# Main.net
KiCad netlist of a schematic drawn in Altium Designer
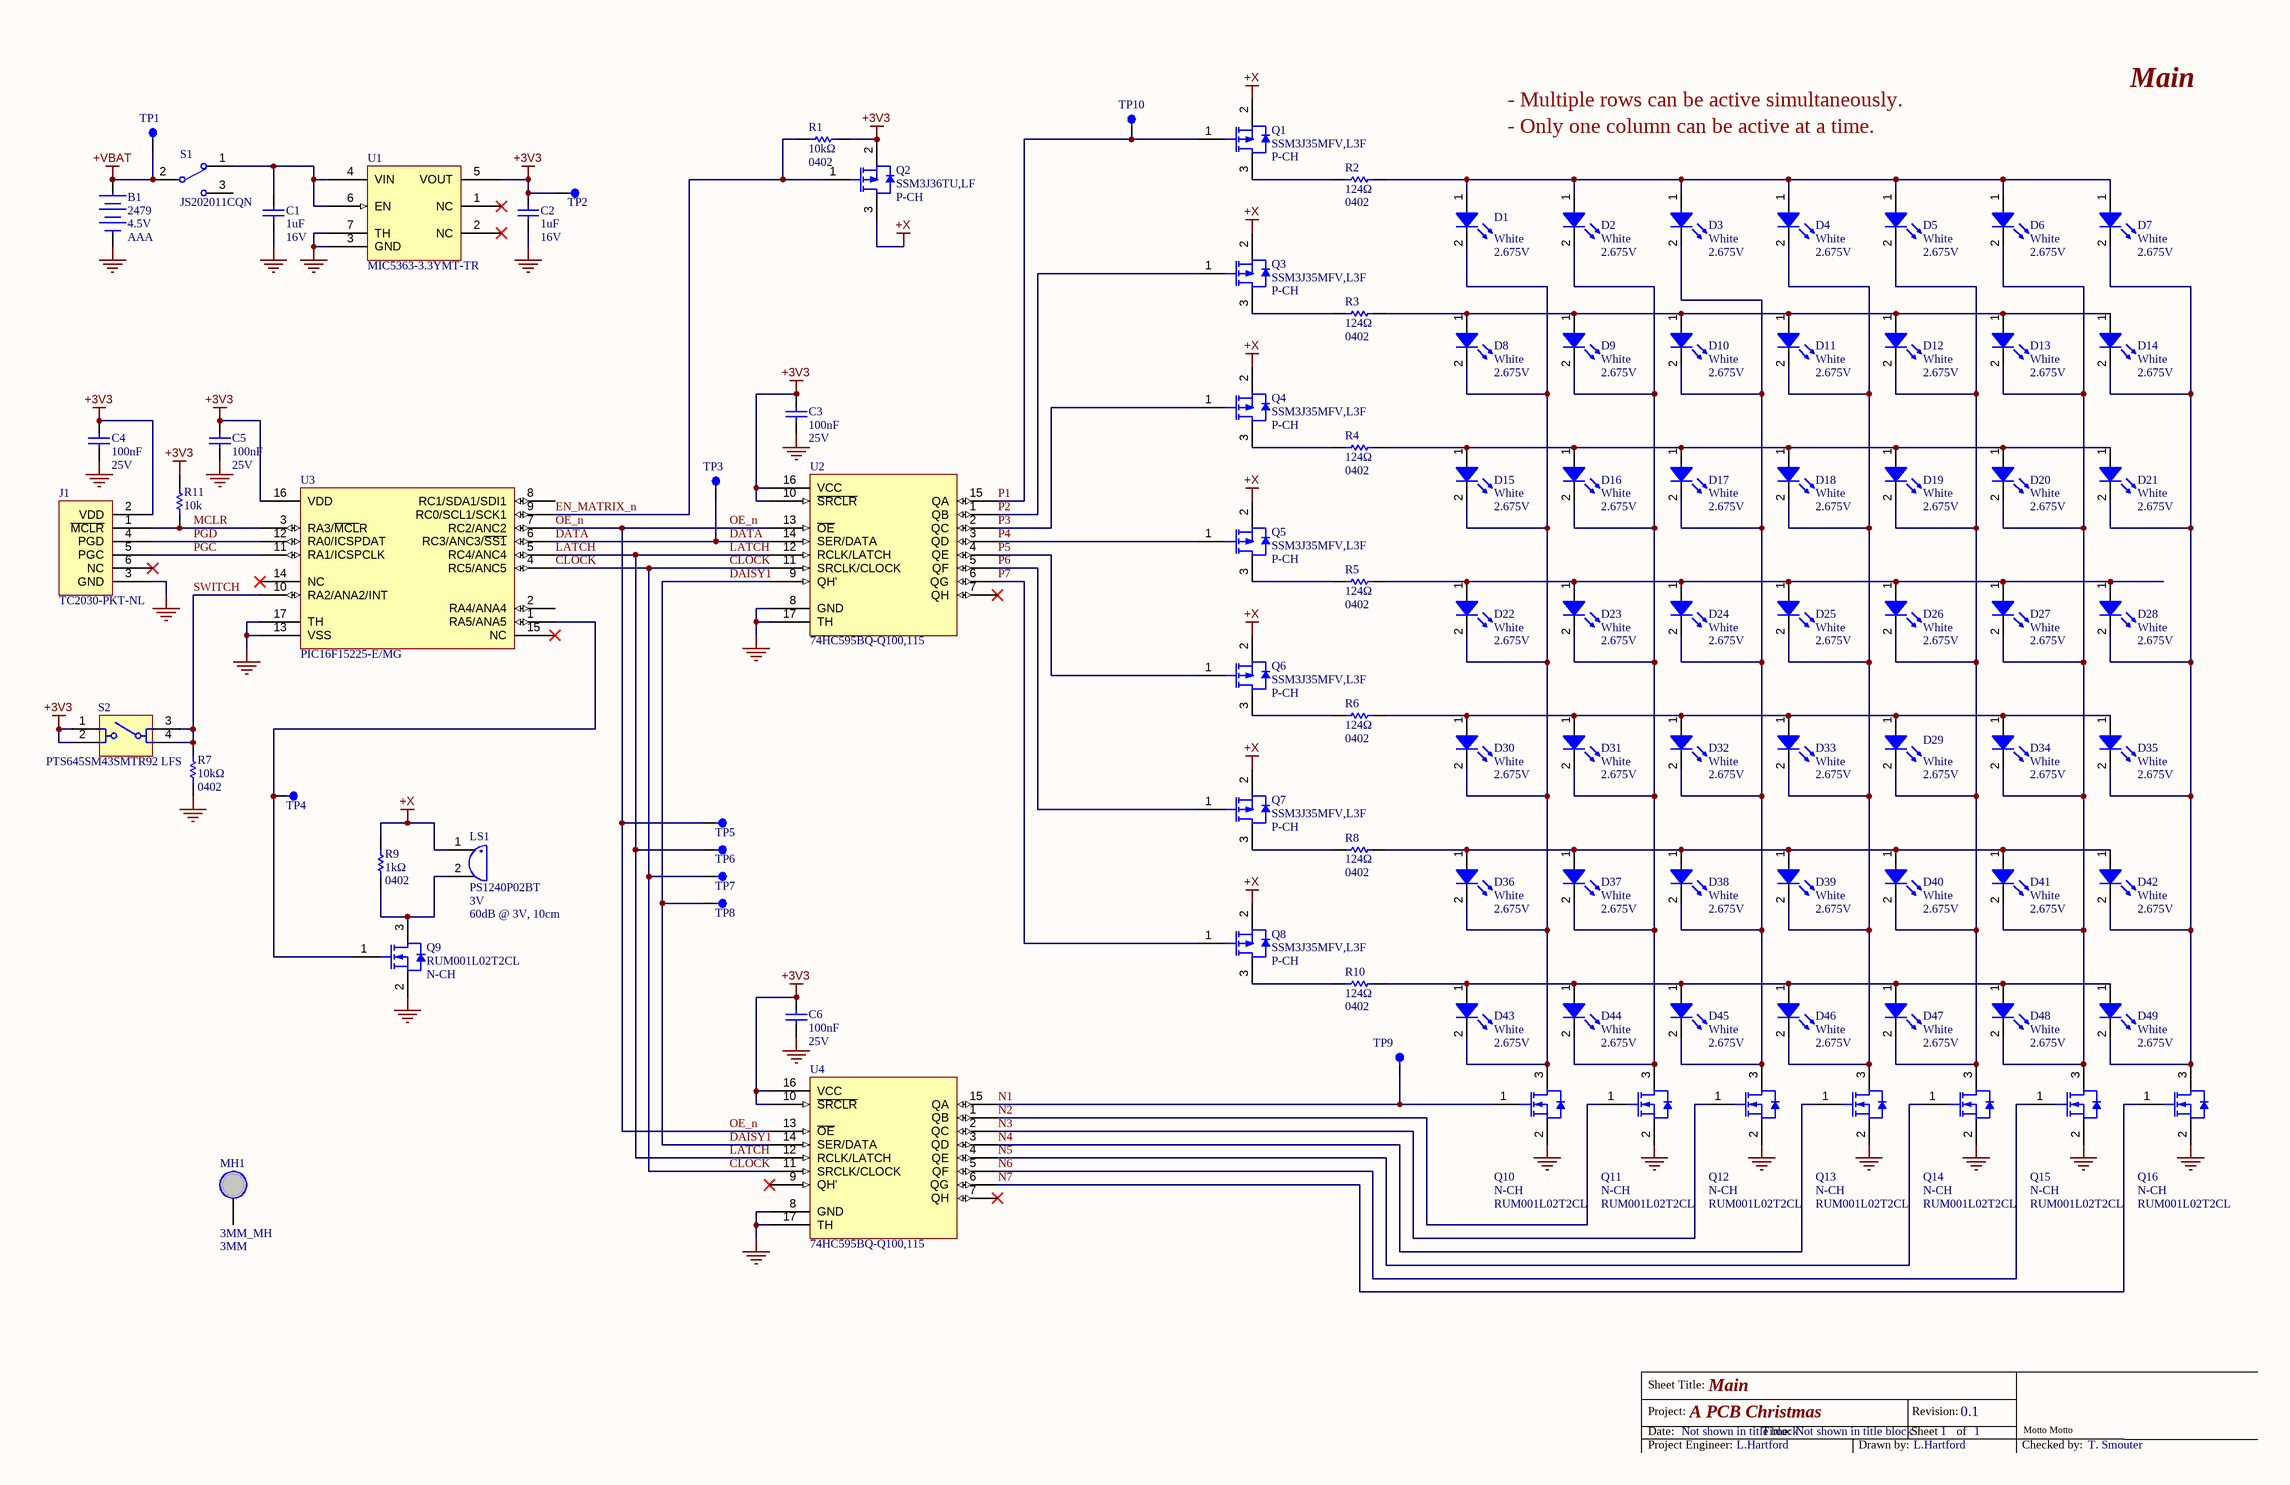
[diagram p0: Main.SchDoc]

(export (version "E")
  (design (tool "Eeschema 10.0.6"))
  (components
    (comp (ref "B1")
      (value "Three Cell")
      (footprint "2479")
      (fields
        (field (name "=MANUFACTURER PART NUMBER") "2479")
        (field (name "V") "4.5V")
        (field (name "SERIES") "AAA")
        (field (name "PART NUMBER") "2479")
        (field (name "VOLTAGE") "4.5V")
      )
      (libsource (lib "altium-db-library") (part "Three Cell"))
    )
    (comp (ref "C1")
      (value "1uF")
      (footprint "C0402")
      (fields
        (field (name "VOLTAGE") "16V")
        (field (name "PART NUMBER") "CL05A105KO5NNNC")
        (field (name "MANUFACTURER") "Samsung Electro-Mechanics")
        (field (name "Comment") "Ceramic Cap")
      )
      (libsource (lib "altium-db-library") (part "Ceramic Cap"))
    )
    (comp (ref "C2")
      (value "1uF")
      (footprint "C0402")
      (fields
        (field (name "VOLTAGE") "16V")
        (field (name "PART NUMBER") "CL05A105KO5NNNC")
        (field (name "MANUFACTURER") "Samsung Electro-Mechanics")
        (field (name "Comment") "Ceramic Cap")
      )
      (libsource (lib "altium-db-library") (part "Ceramic Cap"))
    )
    (comp (ref "C3")
      (value "100nF")
      (footprint "C0402")
      (fields
        (field (name "VOLTAGE") "25V")
        (field (name "PART NUMBER") "CL05A104KA5NNNC")
        (field (name "MANUFACTURER") "Samsung Electro-Mechanics")
        (field (name "Comment") "Ceramic Cap")
      )
      (libsource (lib "altium-db-library") (part "Ceramic Cap"))
    )
    (comp (ref "C4")
      (value "100nF")
      (footprint "C0402")
      (fields
        (field (name "VOLTAGE") "25V")
        (field (name "PART NUMBER") "CL05A104KA5NNNC")
        (field (name "MANUFACTURER") "Samsung Electro-Mechanics")
        (field (name "Comment") "Ceramic Cap")
      )
      (libsource (lib "altium-db-library") (part "Ceramic Cap"))
    )
    (comp (ref "C5")
      (value "100nF")
      (footprint "C0402")
      (fields
        (field (name "VOLTAGE") "25V")
        (field (name "PART NUMBER") "CL05A104KA5NNNC")
        (field (name "MANUFACTURER") "Samsung Electro-Mechanics")
        (field (name "Comment") "Ceramic Cap")
      )
      (libsource (lib "altium-db-library") (part "Ceramic Cap"))
    )
    (comp (ref "C6")
      (value "100nF")
      (footprint "C0402")
      (fields
        (field (name "VOLTAGE") "25V")
        (field (name "PART NUMBER") "CL05A104KA5NNNC")
        (field (name "MANUFACTURER") "Samsung Electro-Mechanics")
        (field (name "Comment") "Ceramic Cap")
      )
      (libsource (lib "altium-db-library") (part "Ceramic Cap"))
    )
    (comp (ref "D1")
      (value "LED")
      (footprint "16-219AUTD/S3151/TR8")
      (fields
        (field (name "MANUFACTURER PART NUMBER") "16-219AUTD/S3151/TR8")
        (field (name "COLOR") "White")
        (field (name "FORWARD") "2.675V")
      )
      (libsource (lib "altium-db-library") (part "LED"))
    )
    (comp (ref "D2")
      (value "LED")
      (footprint "16-219AUTD/S3151/TR8")
      (fields
        (field (name "MANUFACTURER PART NUMBER") "16-219AUTD/S3151/TR8")
        (field (name "COLOR") "White")
        (field (name "FORWARD") "2.675V")
      )
      (libsource (lib "altium-db-library") (part "LED"))
    )
    (comp (ref "D3")
      (value "LED")
      (footprint "16-219AUTD/S3151/TR8")
      (fields
        (field (name "MANUFACTURER PART NUMBER") "16-219AUTD/S3151/TR8")
        (field (name "COLOR") "White")
        (field (name "FORWARD") "2.675V")
      )
      (libsource (lib "altium-db-library") (part "LED"))
    )
    (comp (ref "D4")
      (value "LED")
      (footprint "16-219AUTD/S3151/TR8")
      (fields
        (field (name "MANUFACTURER PART NUMBER") "16-219AUTD/S3151/TR8")
        (field (name "COLOR") "White")
        (field (name "FORWARD") "2.675V")
      )
      (libsource (lib "altium-db-library") (part "LED"))
    )
    (comp (ref "D5")
      (value "LED")
      (footprint "16-219AUTD/S3151/TR8")
      (fields
        (field (name "MANUFACTURER PART NUMBER") "16-219AUTD/S3151/TR8")
        (field (name "COLOR") "White")
        (field (name "FORWARD") "2.675V")
      )
      (libsource (lib "altium-db-library") (part "LED"))
    )
    (comp (ref "D6")
      (value "LED")
      (footprint "16-219AUTD/S3151/TR8")
      (fields
        (field (name "MANUFACTURER PART NUMBER") "16-219AUTD/S3151/TR8")
        (field (name "COLOR") "White")
        (field (name "FORWARD") "2.675V")
      )
      (libsource (lib "altium-db-library") (part "LED"))
    )
    (comp (ref "D7")
      (value "LED")
      (footprint "16-219AUTD/S3151/TR8")
      (fields
        (field (name "MANUFACTURER PART NUMBER") "16-219AUTD/S3151/TR8")
        (field (name "COLOR") "White")
        (field (name "FORWARD") "2.675V")
      )
      (libsource (lib "altium-db-library") (part "LED"))
    )
    (comp (ref "D8")
      (value "LED")
      (footprint "16-219AUTD/S3151/TR8")
      (fields
        (field (name "MANUFACTURER PART NUMBER") "16-219AUTD/S3151/TR8")
        (field (name "COLOR") "White")
        (field (name "FORWARD") "2.675V")
      )
      (libsource (lib "altium-db-library") (part "LED"))
    )
    (comp (ref "D9")
      (value "LED")
      (footprint "16-219AUTD/S3151/TR8")
      (fields
        (field (name "MANUFACTURER PART NUMBER") "16-219AUTD/S3151/TR8")
        (field (name "COLOR") "White")
        (field (name "FORWARD") "2.675V")
      )
      (libsource (lib "altium-db-library") (part "LED"))
    )
    (comp (ref "D10")
      (value "LED")
      (footprint "16-219AUTD/S3151/TR8")
      (fields
        (field (name "MANUFACTURER PART NUMBER") "16-219AUTD/S3151/TR8")
        (field (name "COLOR") "White")
        (field (name "FORWARD") "2.675V")
      )
      (libsource (lib "altium-db-library") (part "LED"))
    )
    (comp (ref "D11")
      (value "LED")
      (footprint "16-219AUTD/S3151/TR8")
      (fields
        (field (name "MANUFACTURER PART NUMBER") "16-219AUTD/S3151/TR8")
        (field (name "COLOR") "White")
        (field (name "FORWARD") "2.675V")
      )
      (libsource (lib "altium-db-library") (part "LED"))
    )
    (comp (ref "D12")
      (value "LED")
      (footprint "16-219AUTD/S3151/TR8")
      (fields
        (field (name "MANUFACTURER PART NUMBER") "16-219AUTD/S3151/TR8")
        (field (name "COLOR") "White")
        (field (name "FORWARD") "2.675V")
      )
      (libsource (lib "altium-db-library") (part "LED"))
    )
    (comp (ref "D13")
      (value "LED")
      (footprint "16-219AUTD/S3151/TR8")
      (fields
        (field (name "MANUFACTURER PART NUMBER") "16-219AUTD/S3151/TR8")
        (field (name "COLOR") "White")
        (field (name "FORWARD") "2.675V")
      )
      (libsource (lib "altium-db-library") (part "LED"))
    )
    (comp (ref "D14")
      (value "LED")
      (footprint "16-219AUTD/S3151/TR8")
      (fields
        (field (name "MANUFACTURER PART NUMBER") "16-219AUTD/S3151/TR8")
        (field (name "COLOR") "White")
        (field (name "FORWARD") "2.675V")
      )
      (libsource (lib "altium-db-library") (part "LED"))
    )
    (comp (ref "D15")
      (value "LED")
      (footprint "16-219AUTD/S3151/TR8")
      (fields
        (field (name "MANUFACTURER PART NUMBER") "16-219AUTD/S3151/TR8")
        (field (name "COLOR") "White")
        (field (name "FORWARD") "2.675V")
      )
      (libsource (lib "altium-db-library") (part "LED"))
    )
    (comp (ref "D16")
      (value "LED")
      (footprint "16-219AUTD/S3151/TR8")
      (fields
        (field (name "MANUFACTURER PART NUMBER") "16-219AUTD/S3151/TR8")
        (field (name "COLOR") "White")
        (field (name "FORWARD") "2.675V")
      )
      (libsource (lib "altium-db-library") (part "LED"))
    )
    (comp (ref "D17")
      (value "LED")
      (footprint "16-219AUTD/S3151/TR8")
      (fields
        (field (name "MANUFACTURER PART NUMBER") "16-219AUTD/S3151/TR8")
        (field (name "COLOR") "White")
        (field (name "FORWARD") "2.675V")
      )
      (libsource (lib "altium-db-library") (part "LED"))
    )
    (comp (ref "D18")
      (value "LED")
      (footprint "16-219AUTD/S3151/TR8")
      (fields
        (field (name "MANUFACTURER PART NUMBER") "16-219AUTD/S3151/TR8")
        (field (name "COLOR") "White")
        (field (name "FORWARD") "2.675V")
      )
      (libsource (lib "altium-db-library") (part "LED"))
    )
    (comp (ref "D19")
      (value "LED")
      (footprint "16-219AUTD/S3151/TR8")
      (fields
        (field (name "MANUFACTURER PART NUMBER") "16-219AUTD/S3151/TR8")
        (field (name "COLOR") "White")
        (field (name "FORWARD") "2.675V")
      )
      (libsource (lib "altium-db-library") (part "LED"))
    )
    (comp (ref "D20")
      (value "LED")
      (footprint "16-219AUTD/S3151/TR8")
      (fields
        (field (name "MANUFACTURER PART NUMBER") "16-219AUTD/S3151/TR8")
        (field (name "COLOR") "White")
        (field (name "FORWARD") "2.675V")
      )
      (libsource (lib "altium-db-library") (part "LED"))
    )
    (comp (ref "D21")
      (value "LED")
      (footprint "16-219AUTD/S3151/TR8")
      (fields
        (field (name "MANUFACTURER PART NUMBER") "16-219AUTD/S3151/TR8")
        (field (name "COLOR") "White")
        (field (name "FORWARD") "2.675V")
      )
      (libsource (lib "altium-db-library") (part "LED"))
    )
    (comp (ref "D22")
      (value "LED")
      (footprint "16-219AUTD/S3151/TR8")
      (fields
        (field (name "MANUFACTURER PART NUMBER") "16-219AUTD/S3151/TR8")
        (field (name "COLOR") "White")
        (field (name "FORWARD") "2.675V")
      )
      (libsource (lib "altium-db-library") (part "LED"))
    )
    (comp (ref "D23")
      (value "LED")
      (footprint "16-219AUTD/S3151/TR8")
      (fields
        (field (name "MANUFACTURER PART NUMBER") "16-219AUTD/S3151/TR8")
        (field (name "COLOR") "White")
        (field (name "FORWARD") "2.675V")
      )
      (libsource (lib "altium-db-library") (part "LED"))
    )
    (comp (ref "D24")
      (value "LED")
      (footprint "16-219AUTD/S3151/TR8")
      (fields
        (field (name "MANUFACTURER PART NUMBER") "16-219AUTD/S3151/TR8")
        (field (name "COLOR") "White")
        (field (name "FORWARD") "2.675V")
      )
      (libsource (lib "altium-db-library") (part "LED"))
    )
    (comp (ref "D25")
      (value "LED")
      (footprint "16-219AUTD/S3151/TR8")
      (fields
        (field (name "MANUFACTURER PART NUMBER") "16-219AUTD/S3151/TR8")
        (field (name "COLOR") "White")
        (field (name "FORWARD") "2.675V")
      )
      (libsource (lib "altium-db-library") (part "LED"))
    )
    (comp (ref "D26")
      (value "LED")
      (footprint "16-219AUTD/S3151/TR8")
      (fields
        (field (name "MANUFACTURER PART NUMBER") "16-219AUTD/S3151/TR8")
        (field (name "COLOR") "White")
        (field (name "FORWARD") "2.675V")
      )
      (libsource (lib "altium-db-library") (part "LED"))
    )
    (comp (ref "D27")
      (value "LED")
      (footprint "16-219AUTD/S3151/TR8")
      (fields
        (field (name "MANUFACTURER PART NUMBER") "16-219AUTD/S3151/TR8")
        (field (name "COLOR") "White")
        (field (name "FORWARD") "2.675V")
      )
      (libsource (lib "altium-db-library") (part "LED"))
    )
    (comp (ref "D28")
      (value "LED")
      (footprint "16-219AUTD/S3151/TR8")
      (fields
        (field (name "MANUFACTURER PART NUMBER") "16-219AUTD/S3151/TR8")
        (field (name "COLOR") "White")
        (field (name "FORWARD") "2.675V")
      )
      (libsource (lib "altium-db-library") (part "LED"))
    )
    (comp (ref "D29")
      (value "LED")
      (footprint "16-219AUTD/S3151/TR8")
      (fields
        (field (name "MANUFACTURER PART NUMBER") "16-219AUTD/S3151/TR8")
        (field (name "COLOR") "White")
        (field (name "FORWARD") "2.675V")
      )
      (libsource (lib "altium-db-library") (part "LED"))
    )
    (comp (ref "D30")
      (value "LED")
      (footprint "16-219AUTD/S3151/TR8")
      (fields
        (field (name "MANUFACTURER PART NUMBER") "16-219AUTD/S3151/TR8")
        (field (name "COLOR") "White")
        (field (name "FORWARD") "2.675V")
      )
      (libsource (lib "altium-db-library") (part "LED"))
    )
    (comp (ref "D31")
      (value "LED")
      (footprint "16-219AUTD/S3151/TR8")
      (fields
        (field (name "MANUFACTURER PART NUMBER") "16-219AUTD/S3151/TR8")
        (field (name "COLOR") "White")
        (field (name "FORWARD") "2.675V")
      )
      (libsource (lib "altium-db-library") (part "LED"))
    )
    (comp (ref "D32")
      (value "LED")
      (footprint "16-219AUTD/S3151/TR8")
      (fields
        (field (name "MANUFACTURER PART NUMBER") "16-219AUTD/S3151/TR8")
        (field (name "COLOR") "White")
        (field (name "FORWARD") "2.675V")
      )
      (libsource (lib "altium-db-library") (part "LED"))
    )
    (comp (ref "D33")
      (value "LED")
      (footprint "16-219AUTD/S3151/TR8")
      (fields
        (field (name "MANUFACTURER PART NUMBER") "16-219AUTD/S3151/TR8")
        (field (name "COLOR") "White")
        (field (name "FORWARD") "2.675V")
      )
      (libsource (lib "altium-db-library") (part "LED"))
    )
    (comp (ref "D34")
      (value "LED")
      (footprint "16-219AUTD/S3151/TR8")
      (fields
        (field (name "MANUFACTURER PART NUMBER") "16-219AUTD/S3151/TR8")
        (field (name "COLOR") "White")
        (field (name "FORWARD") "2.675V")
      )
      (libsource (lib "altium-db-library") (part "LED"))
    )
    (comp (ref "D35")
      (value "LED")
      (footprint "16-219AUTD/S3151/TR8")
      (fields
        (field (name "MANUFACTURER PART NUMBER") "16-219AUTD/S3151/TR8")
        (field (name "COLOR") "White")
        (field (name "FORWARD") "2.675V")
      )
      (libsource (lib "altium-db-library") (part "LED"))
    )
    (comp (ref "D36")
      (value "LED")
      (footprint "16-219AUTD/S3151/TR8")
      (fields
        (field (name "MANUFACTURER PART NUMBER") "16-219AUTD/S3151/TR8")
        (field (name "COLOR") "White")
        (field (name "FORWARD") "2.675V")
      )
      (libsource (lib "altium-db-library") (part "LED"))
    )
    (comp (ref "D37")
      (value "LED")
      (footprint "16-219AUTD/S3151/TR8")
      (fields
        (field (name "MANUFACTURER PART NUMBER") "16-219AUTD/S3151/TR8")
        (field (name "COLOR") "White")
        (field (name "FORWARD") "2.675V")
      )
      (libsource (lib "altium-db-library") (part "LED"))
    )
    (comp (ref "D38")
      (value "LED")
      (footprint "16-219AUTD/S3151/TR8")
      (fields
        (field (name "MANUFACTURER PART NUMBER") "16-219AUTD/S3151/TR8")
        (field (name "COLOR") "White")
        (field (name "FORWARD") "2.675V")
      )
      (libsource (lib "altium-db-library") (part "LED"))
    )
    (comp (ref "D39")
      (value "LED")
      (footprint "16-219AUTD/S3151/TR8")
      (fields
        (field (name "MANUFACTURER PART NUMBER") "16-219AUTD/S3151/TR8")
        (field (name "COLOR") "White")
        (field (name "FORWARD") "2.675V")
      )
      (libsource (lib "altium-db-library") (part "LED"))
    )
    (comp (ref "D40")
      (value "LED")
      (footprint "16-219AUTD/S3151/TR8")
      (fields
        (field (name "MANUFACTURER PART NUMBER") "16-219AUTD/S3151/TR8")
        (field (name "COLOR") "White")
        (field (name "FORWARD") "2.675V")
      )
      (libsource (lib "altium-db-library") (part "LED"))
    )
    (comp (ref "D41")
      (value "LED")
      (footprint "16-219AUTD/S3151/TR8")
      (fields
        (field (name "MANUFACTURER PART NUMBER") "16-219AUTD/S3151/TR8")
        (field (name "COLOR") "White")
        (field (name "FORWARD") "2.675V")
      )
      (libsource (lib "altium-db-library") (part "LED"))
    )
    (comp (ref "D42")
      (value "LED")
      (footprint "16-219AUTD/S3151/TR8")
      (fields
        (field (name "MANUFACTURER PART NUMBER") "16-219AUTD/S3151/TR8")
        (field (name "COLOR") "White")
        (field (name "FORWARD") "2.675V")
      )
      (libsource (lib "altium-db-library") (part "LED"))
    )
    (comp (ref "D43")
      (value "LED")
      (footprint "16-219AUTD/S3151/TR8")
      (fields
        (field (name "MANUFACTURER PART NUMBER") "16-219AUTD/S3151/TR8")
        (field (name "COLOR") "White")
        (field (name "FORWARD") "2.675V")
      )
      (libsource (lib "altium-db-library") (part "LED"))
    )
    (comp (ref "D44")
      (value "LED")
      (footprint "16-219AUTD/S3151/TR8")
      (fields
        (field (name "MANUFACTURER PART NUMBER") "16-219AUTD/S3151/TR8")
        (field (name "COLOR") "White")
        (field (name "FORWARD") "2.675V")
      )
      (libsource (lib "altium-db-library") (part "LED"))
    )
    (comp (ref "D45")
      (value "LED")
      (footprint "16-219AUTD/S3151/TR8")
      (fields
        (field (name "MANUFACTURER PART NUMBER") "16-219AUTD/S3151/TR8")
        (field (name "COLOR") "White")
        (field (name "FORWARD") "2.675V")
      )
      (libsource (lib "altium-db-library") (part "LED"))
    )
    (comp (ref "D46")
      (value "LED")
      (footprint "16-219AUTD/S3151/TR8")
      (fields
        (field (name "MANUFACTURER PART NUMBER") "16-219AUTD/S3151/TR8")
        (field (name "COLOR") "White")
        (field (name "FORWARD") "2.675V")
      )
      (libsource (lib "altium-db-library") (part "LED"))
    )
    (comp (ref "D47")
      (value "LED")
      (footprint "16-219AUTD/S3151/TR8")
      (fields
        (field (name "MANUFACTURER PART NUMBER") "16-219AUTD/S3151/TR8")
        (field (name "COLOR") "White")
        (field (name "FORWARD") "2.675V")
      )
      (libsource (lib "altium-db-library") (part "LED"))
    )
    (comp (ref "D48")
      (value "LED")
      (footprint "16-219AUTD/S3151/TR8")
      (fields
        (field (name "MANUFACTURER PART NUMBER") "16-219AUTD/S3151/TR8")
        (field (name "COLOR") "White")
        (field (name "FORWARD") "2.675V")
      )
      (libsource (lib "altium-db-library") (part "LED"))
    )
    (comp (ref "D49")
      (value "LED")
      (footprint "16-219AUTD/S3151/TR8")
      (fields
        (field (name "MANUFACTURER PART NUMBER") "16-219AUTD/S3151/TR8")
        (field (name "COLOR") "White")
        (field (name "FORWARD") "2.675V")
      )
      (libsource (lib "altium-db-library") (part "LED"))
    )
    (comp (ref "J1")
      (value "TC2030-PKT-NL")
      (footprint "TC2030-PKT-NL")
      (description "No Clip 6 Pin Tag Connect")
      (fields (field (name "MANUFACTURER") "Tag-Connect LLC"))
      (libsource (lib "altium-db-library") (part "TC2030-PKT-NL"))
    )
    (comp (ref "LS1")
      (value "Buzzer")
      (footprint "PS1240P02BT")
      (fields
        (field (name "MANUFACTURER PART NUMBER") "PS1240P02BT")
        (field (name "VOLTAGE") "3V")
        (field (name "SOUND PRESSURE LEVEL") "60dB @ 3V, 10cm")
        (field (name "PART NUMBER") "PS1240P02BT")
      )
      (libsource (lib "altium-db-library") (part "Buzzer"))
    )
    (comp (ref "MH1")
      (value "3MM_MH")
      (footprint "3MM_MH")
      (fields (field (name "SIZE") "3MM"))
      (libsource (lib "altium-db-library") (part "3MM_MH"))
    )
    (comp (ref "Q1")
      (value "P-CH")
      (footprint "SOTFL40P120X55-3N-2")
      (fields
        (field (name "MANUFACTURER PART NUMBER") "SSM3J35MFV,L3F")
        (field (name "FET TYPE") "P-CH")
        (field (name "PART NUMBER") "SSM3J35MFV,L3F")
        (field (name "MANUFACTURER") "Toshiba Semiconductor and Storage")
      )
      (libsource (lib "altium-db-library") (part "P-CH"))
    )
    (comp (ref "Q2")
      (value "P-CH")
      (footprint "SOTFL65P210X75-3N")
      (fields
        (field (name "MANUFACTURER PART NUMBER") "SSM3J36TU,LF")
        (field (name "FET TYPE") "P-CH")
        (field (name "PART NUMBER") "SSM3J36TU,LF")
        (field (name "MANUFACTURER") "Toshiba Semiconductor and Storage")
      )
      (libsource (lib "altium-db-library") (part "P-CH"))
    )
    (comp (ref "Q3")
      (value "P-CH")
      (footprint "SOTFL40P120X55-3N-2")
      (fields
        (field (name "MANUFACTURER PART NUMBER") "SSM3J35MFV,L3F")
        (field (name "FET TYPE") "P-CH")
        (field (name "PART NUMBER") "SSM3J35MFV,L3F")
        (field (name "MANUFACTURER") "Toshiba Semiconductor and Storage")
      )
      (libsource (lib "altium-db-library") (part "P-CH"))
    )
    (comp (ref "Q4")
      (value "P-CH")
      (footprint "SOTFL40P120X55-3N-2")
      (fields
        (field (name "MANUFACTURER PART NUMBER") "SSM3J35MFV,L3F")
        (field (name "FET TYPE") "P-CH")
        (field (name "PART NUMBER") "SSM3J35MFV,L3F")
        (field (name "MANUFACTURER") "Toshiba Semiconductor and Storage")
      )
      (libsource (lib "altium-db-library") (part "P-CH"))
    )
    (comp (ref "Q5")
      (value "P-CH")
      (footprint "SOTFL40P120X55-3N-2")
      (fields
        (field (name "MANUFACTURER PART NUMBER") "SSM3J35MFV,L3F")
        (field (name "FET TYPE") "P-CH")
        (field (name "PART NUMBER") "SSM3J35MFV,L3F")
        (field (name "MANUFACTURER") "Toshiba Semiconductor and Storage")
      )
      (libsource (lib "altium-db-library") (part "P-CH"))
    )
    (comp (ref "Q6")
      (value "P-CH")
      (footprint "SOTFL40P120X55-3N-2")
      (fields
        (field (name "MANUFACTURER PART NUMBER") "SSM3J35MFV,L3F")
        (field (name "FET TYPE") "P-CH")
        (field (name "PART NUMBER") "SSM3J35MFV,L3F")
        (field (name "MANUFACTURER") "Toshiba Semiconductor and Storage")
      )
      (libsource (lib "altium-db-library") (part "P-CH"))
    )
    (comp (ref "Q7")
      (value "P-CH")
      (footprint "SOTFL40P120X55-3N-2")
      (fields
        (field (name "MANUFACTURER PART NUMBER") "SSM3J35MFV,L3F")
        (field (name "FET TYPE") "P-CH")
        (field (name "PART NUMBER") "SSM3J35MFV,L3F")
        (field (name "MANUFACTURER") "Toshiba Semiconductor and Storage")
      )
      (libsource (lib "altium-db-library") (part "P-CH"))
    )
    (comp (ref "Q8")
      (value "P-CH")
      (footprint "SOTFL40P120X55-3N-2")
      (fields
        (field (name "MANUFACTURER PART NUMBER") "SSM3J35MFV,L3F")
        (field (name "FET TYPE") "P-CH")
        (field (name "PART NUMBER") "SSM3J35MFV,L3F")
        (field (name "MANUFACTURER") "Toshiba Semiconductor and Storage")
      )
      (libsource (lib "altium-db-library") (part "P-CH"))
    )
    (comp (ref "Q9")
      (value "N-CH")
      (footprint "SOTFL40P120X55-3N")
      (fields
        (field (name "MANUFACTURER PART NUMBER") "RUM001L02T2CL")
        (field (name "FET TYPE") "N-CH")
        (field (name "PART NUMBER") "RUM001L02T2CL")
        (field (name "MANUFACTURER") "Rohm Semiconductor")
      )
      (libsource (lib "altium-db-library") (part "N-CH"))
    )
    (comp (ref "Q10")
      (value "N-CH")
      (footprint "SOTFL40P120X55-3N")
      (fields
        (field (name "MANUFACTURER PART NUMBER") "RUM001L02T2CL")
        (field (name "FET TYPE") "N-CH")
        (field (name "PART NUMBER") "RUM001L02T2CL")
        (field (name "MANUFACTURER") "Rohm Semiconductor")
      )
      (libsource (lib "altium-db-library") (part "N-CH"))
    )
    (comp (ref "Q11")
      (value "N-CH")
      (footprint "SOTFL40P120X55-3N")
      (fields
        (field (name "MANUFACTURER PART NUMBER") "RUM001L02T2CL")
        (field (name "FET TYPE") "N-CH")
        (field (name "PART NUMBER") "RUM001L02T2CL")
        (field (name "MANUFACTURER") "Rohm Semiconductor")
      )
      (libsource (lib "altium-db-library") (part "N-CH"))
    )
    (comp (ref "Q12")
      (value "N-CH")
      (footprint "SOTFL40P120X55-3N")
      (fields
        (field (name "MANUFACTURER PART NUMBER") "RUM001L02T2CL")
        (field (name "FET TYPE") "N-CH")
        (field (name "PART NUMBER") "RUM001L02T2CL")
        (field (name "MANUFACTURER") "Rohm Semiconductor")
      )
      (libsource (lib "altium-db-library") (part "N-CH"))
    )
    (comp (ref "Q13")
      (value "N-CH")
      (footprint "SOTFL40P120X55-3N")
      (fields
        (field (name "MANUFACTURER PART NUMBER") "RUM001L02T2CL")
        (field (name "FET TYPE") "N-CH")
        (field (name "PART NUMBER") "RUM001L02T2CL")
        (field (name "MANUFACTURER") "Rohm Semiconductor")
      )
      (libsource (lib "altium-db-library") (part "N-CH"))
    )
    (comp (ref "Q14")
      (value "N-CH")
      (footprint "SOTFL40P120X55-3N")
      (fields
        (field (name "MANUFACTURER PART NUMBER") "RUM001L02T2CL")
        (field (name "FET TYPE") "N-CH")
        (field (name "PART NUMBER") "RUM001L02T2CL")
        (field (name "MANUFACTURER") "Rohm Semiconductor")
      )
      (libsource (lib "altium-db-library") (part "N-CH"))
    )
    (comp (ref "Q15")
      (value "N-CH")
      (footprint "SOTFL40P120X55-3N")
      (fields
        (field (name "MANUFACTURER PART NUMBER") "RUM001L02T2CL")
        (field (name "FET TYPE") "N-CH")
        (field (name "PART NUMBER") "RUM001L02T2CL")
        (field (name "MANUFACTURER") "Rohm Semiconductor")
      )
      (libsource (lib "altium-db-library") (part "N-CH"))
    )
    (comp (ref "Q16")
      (value "N-CH")
      (footprint "SOTFL40P120X55-3N")
      (fields
        (field (name "MANUFACTURER PART NUMBER") "RUM001L02T2CL")
        (field (name "FET TYPE") "N-CH")
        (field (name "PART NUMBER") "RUM001L02T2CL")
        (field (name "MANUFACTURER") "Rohm Semiconductor")
      )
      (libsource (lib "altium-db-library") (part "N-CH"))
    )
    (comp (ref "R1")
      (value "10kΩ")
      (footprint "RESC1005X04N")
      (fields
        (field (name "PACKAGE/FOOTPRINT") "0402")
        (field (name "PART NUMBER") "RMCF0402FT10K0")
        (field (name "MANUFACTURER") "Stackpole Electronics Inc")
        (field (name "Comment") "Resistor")
      )
      (libsource (lib "altium-db-library") (part "Resistor"))
    )
    (comp (ref "R2")
      (value "124Ω")
      (footprint "RESC1005X04N")
      (fields
        (field (name "PACKAGE/FOOTPRINT") "0402")
        (field (name "PART NUMBER") "ERJ-2RKF1240X")
        (field (name "MANUFACTURER") "Panasonic Electronic Components")
        (field (name "Comment") "Resistor")
      )
      (libsource (lib "altium-db-library") (part "Resistor"))
    )
    (comp (ref "R3")
      (value "124Ω")
      (footprint "RESC1005X04N")
      (fields
        (field (name "PACKAGE/FOOTPRINT") "0402")
        (field (name "PART NUMBER") "ERJ-2RKF1240X")
        (field (name "MANUFACTURER") "Panasonic Electronic Components")
        (field (name "Comment") "Resistor")
      )
      (libsource (lib "altium-db-library") (part "Resistor"))
    )
    (comp (ref "R4")
      (value "124Ω")
      (footprint "RESC1005X04N")
      (fields
        (field (name "PACKAGE/FOOTPRINT") "0402")
        (field (name "PART NUMBER") "ERJ-2RKF1240X")
        (field (name "MANUFACTURER") "Panasonic Electronic Components")
        (field (name "Comment") "Resistor")
      )
      (libsource (lib "altium-db-library") (part "Resistor"))
    )
    (comp (ref "R5")
      (value "124Ω")
      (footprint "RESC1005X04N")
      (fields
        (field (name "PACKAGE/FOOTPRINT") "0402")
        (field (name "PART NUMBER") "ERJ-2RKF1240X")
        (field (name "MANUFACTURER") "Panasonic Electronic Components")
        (field (name "Comment") "Resistor")
      )
      (libsource (lib "altium-db-library") (part "Resistor"))
    )
    (comp (ref "R6")
      (value "124Ω")
      (footprint "RESC1005X04N")
      (fields
        (field (name "PACKAGE/FOOTPRINT") "0402")
        (field (name "PART NUMBER") "ERJ-2RKF1240X")
        (field (name "MANUFACTURER") "Panasonic Electronic Components")
        (field (name "Comment") "Resistor")
      )
      (libsource (lib "altium-db-library") (part "Resistor"))
    )
    (comp (ref "R7")
      (value "10kΩ")
      (footprint "RESC1005X04N")
      (fields
        (field (name "PACKAGE/FOOTPRINT") "0402")
        (field (name "PART NUMBER") "RMCF0402FT10K0")
        (field (name "MANUFACTURER") "Stackpole Electronics Inc")
        (field (name "Comment") "Resistor")
      )
      (libsource (lib "altium-db-library") (part "Resistor"))
    )
    (comp (ref "R8")
      (value "124Ω")
      (footprint "RESC1005X04N")
      (fields
        (field (name "PACKAGE/FOOTPRINT") "0402")
        (field (name "PART NUMBER") "ERJ-2RKF1240X")
        (field (name "MANUFACTURER") "Panasonic Electronic Components")
        (field (name "Comment") "Resistor")
      )
      (libsource (lib "altium-db-library") (part "Resistor"))
    )
    (comp (ref "R9")
      (value "1kΩ")
      (footprint "RESC1005X04N")
      (fields
        (field (name "PACKAGE/FOOTPRINT") "0402")
        (field (name "PART NUMBER") "RC0402FR-071RL")
        (field (name "MANUFACTURER") "Yageo")
        (field (name "Comment") "Resistor")
      )
      (libsource (lib "altium-db-library") (part "Resistor"))
    )
    (comp (ref "R10")
      (value "124Ω")
      (footprint "RESC1005X04N")
      (fields
        (field (name "PACKAGE/FOOTPRINT") "0402")
        (field (name "PART NUMBER") "ERJ-2RKF1240X")
        (field (name "MANUFACTURER") "Panasonic Electronic Components")
        (field (name "Comment") "Resistor")
      )
      (libsource (lib "altium-db-library") (part "Resistor"))
    )
    (comp (ref "R11")
      (value "10k")
      (footprint "RESC1005X04N")
      (description "RES SMD 10K OHM 1% 1/16W 0402")
      (fields (field (name "PART NUMBER") "RC0402FR-0710KL") (field (name "MANUFACTURER") "Yageo"))
      (libsource (lib "EMRLibrary") (part "RC0402"))
    )
    (comp (ref "S1")
      (value "JS202011CQN")
      (footprint "JS202011CQN")
      (libsource (lib "altium-db-library") (part "JS202011CQN"))
    )
    (comp (ref "S2")
      (value "PTS645SM43SMTR92 LFS")
      (footprint "PTS645SM43SMTR92 LFS")
      (description "SWITCH TACTILE SPST-NO 0.05A 12V")
      (fields
        (field (name "PART NUMBER") "PTS645SK50SMTR92LFS")
        (field (name "MANUFACTURER") "ITT /  C&K Components")
      )
      (libsource (lib "altium-db-library") (part "PTS645SM43SMTR92 LFS"))
    )
    (comp (ref "TP1")
      (value "TP")
      (footprint "ORNAMENTS")
      (fields (field (name "PART NUMBER") "ORNAMENTS"))
      (libsource (lib "altium-db-library") (part "TP"))
    )
    (comp (ref "TP2")
      (value "TP")
      (footprint "ORNAMENTS")
      (fields (field (name "PART NUMBER") "ORNAMENTS"))
      (libsource (lib "altium-db-library") (part "TP"))
    )
    (comp (ref "TP3")
      (value "TP")
      (footprint "ORNAMENTS")
      (fields (field (name "PART NUMBER") "ORNAMENTS"))
      (libsource (lib "altium-db-library") (part "TP"))
    )
    (comp (ref "TP4")
      (value "TP")
      (footprint "ORNAMENTS")
      (fields (field (name "PART NUMBER") "ORNAMENTS"))
      (libsource (lib "altium-db-library") (part "TP"))
    )
    (comp (ref "TP5")
      (value "TP")
      (footprint "ORNAMENTS")
      (fields (field (name "PART NUMBER") "ORNAMENTS"))
      (libsource (lib "altium-db-library") (part "TP"))
    )
    (comp (ref "TP6")
      (value "TP")
      (footprint "ORNAMENTS")
      (fields (field (name "PART NUMBER") "ORNAMENTS"))
      (libsource (lib "altium-db-library") (part "TP"))
    )
    (comp (ref "TP7")
      (value "TP")
      (footprint "ORNAMENTS")
      (fields (field (name "PART NUMBER") "ORNAMENTS"))
      (libsource (lib "altium-db-library") (part "TP"))
    )
    (comp (ref "TP8")
      (value "TP")
      (footprint "ORNAMENTS")
      (fields (field (name "PART NUMBER") "ORNAMENTS"))
      (libsource (lib "altium-db-library") (part "TP"))
    )
    (comp (ref "TP9")
      (value "TP")
      (footprint "ORNAMENTS")
      (fields (field (name "PART NUMBER") "ORNAMENTS"))
      (libsource (lib "altium-db-library") (part "TP"))
    )
    (comp (ref "TP10")
      (value "TP")
      (footprint "ORNAMENTS")
      (fields (field (name "PART NUMBER") "ORNAMENTS"))
      (libsource (lib "altium-db-library") (part "TP"))
    )
    (comp (ref "U1")
      (value "MIC5363-3.3YMT-TR")
      (footprint "QFN40P120X120X60_HS-7N")
      (fields (field (name "MANUFACTURER") "Microchip Technology"))
      (libsource (lib "altium-db-library") (part "MIC5363-3.3YMT-TR"))
    )
    (comp (ref "U2")
      (value "74HC595BQ-Q100,115")
      (footprint "QFN50P250X350X100_HS-17N")
      (fields (field (name "MANUFACTURER") "Nexperia USA Inc."))
      (libsource (lib "altium-db-library") (part "74HC595BQ-Q100,115"))
    )
    (comp (ref "U3")
      (value "PIC16F15225-E/MG")
      (footprint "PQFN50P300X300X90_HS-17N")
      (fields
        (field (name "MANUFACTURER PART NUMBER") "PIC16F15225-E/MG")
        (field (name "MANUFACTURER") "Microchip Technology")
      )
      (libsource (lib "altium-db-library") (part "PIC16F15225-E/MG"))
    )
    (comp (ref "U4")
      (value "74HC595BQ-Q100,115")
      (footprint "QFN50P250X350X100_HS-17N")
      (fields (field (name "MANUFACTURER") "Nexperia USA Inc."))
      (libsource (lib "altium-db-library") (part "74HC595BQ-Q100,115"))
    )
  )
  (nets
    (net (code "1") (name "+3V3") (class "Default")
      (node (ref "C2") (pin "2") (pinfunction "2_2") (pintype "passive"))
      (node (ref "C3") (pin "2") (pinfunction "2_2") (pintype "passive"))
      (node (ref "C4") (pin "2") (pinfunction "2_2") (pintype "passive"))
      (node (ref "C5") (pin "2") (pinfunction "2_2") (pintype "passive"))
      (node (ref "C6") (pin "2") (pinfunction "2_2") (pintype "passive"))
      (node (ref "J1") (pin "2") (pinfunction "VDD_2") (pintype "passive"))
      (node (ref "Q2") (pin "2") (pinfunction "S_2") (pintype "passive"))
      (node (ref "R1") (pin "2") (pinfunction "2_2") (pintype "passive"))
      (node (ref "R11") (pin "2") (pinfunction "2_2") (pintype "passive"))
      (node (ref "S2") (pin "1") (pinfunction "1_1") (pintype "passive"))
      (node (ref "S2") (pin "2") (pinfunction "2_2") (pintype "passive"))
      (node (ref "TP2") (pin "1") (pinfunction "A_1") (pintype "passive"))
      (node (ref "U1") (pin "5") (pinfunction "VOUT_5") (pintype "power_in"))
      (node (ref "U2") (pin "10") (pinfunction "~{SRCLR}_10") (pintype "input"))
      (node (ref "U2") (pin "16") (pinfunction "VCC_16") (pintype "power_in"))
      (node (ref "U3") (pin "16") (pinfunction "VDD_16") (pintype "power_in"))
      (node (ref "U4") (pin "10") (pinfunction "~{SRCLR}_10") (pintype "input"))
      (node (ref "U4") (pin "16") (pinfunction "VCC_16") (pintype "power_in"))
    )
    (net (code "2") (name "+VBAT") (class "Default")
      (node (ref "B1") (pin "1") (pinfunction "+_1") (pintype "passive"))
      (node (ref "S1") (pin "2") (pintype "passive"))
      (node (ref "TP1") (pin "1") (pinfunction "A_1") (pintype "passive"))
    )
    (net (code "3") (name "+X") (class "Default")
      (node (ref "LS1") (pin "1") (pinfunction "+_1") (pintype "power_in"))
      (node (ref "Q1") (pin "2") (pinfunction "S_2") (pintype "passive"))
      (node (ref "Q2") (pin "3") (pinfunction "D_3") (pintype "passive"))
      (node (ref "Q3") (pin "2") (pinfunction "S_2") (pintype "passive"))
      (node (ref "Q4") (pin "2") (pinfunction "S_2") (pintype "passive"))
      (node (ref "Q5") (pin "2") (pinfunction "S_2") (pintype "passive"))
      (node (ref "Q6") (pin "2") (pinfunction "S_2") (pintype "passive"))
      (node (ref "Q7") (pin "2") (pinfunction "S_2") (pintype "passive"))
      (node (ref "Q8") (pin "2") (pinfunction "S_2") (pintype "passive"))
      (node (ref "R9") (pin "2") (pinfunction "2_2") (pintype "passive"))
    )
    (net (code "4") (name "/CLOCK") (class "Default")
      (node (ref "TP7") (pin "1") (pinfunction "A_1") (pintype "passive"))
      (node (ref "U2") (pin "11") (pinfunction "SRCLK/CLOCK_11") (pintype "input"))
      (node (ref "U3") (pin "4") (pinfunction "RC5/ANC5_4") (pintype "bidirectional"))
      (node (ref "U4") (pin "11") (pinfunction "SRCLK/CLOCK_11") (pintype "input"))
    )
    (net (code "5") (name "/DAISY1") (class "Default")
      (node (ref "TP8") (pin "1") (pinfunction "A_1") (pintype "passive"))
      (node (ref "U2") (pin "9") (pinfunction "QH'_9") (pintype "input"))
      (node (ref "U4") (pin "14") (pinfunction "SER/DATA_14") (pintype "input"))
    )
    (net (code "6") (name "/DATA") (class "Default")
      (node (ref "TP3") (pin "1") (pinfunction "A_1") (pintype "passive"))
      (node (ref "U2") (pin "14") (pinfunction "SER/DATA_14") (pintype "input"))
      (node (ref "U3") (pin "6") (pinfunction "RC3/ANC3/~{SS1}_6") (pintype "bidirectional"))
    )
    (net (code "7") (name "/EN_MATRIX_n") (class "Default")
      (node (ref "Q2") (pin "1") (pinfunction "G_1") (pintype "passive"))
      (node (ref "R1") (pin "1") (pinfunction "1_1") (pintype "passive"))
      (node (ref "U3") (pin "9") (pinfunction "RC0/SCL1/SCK1_9") (pintype "bidirectional"))
    )
    (net (code "8") (name "/LATCH") (class "Default")
      (node (ref "TP6") (pin "1") (pinfunction "A_1") (pintype "passive"))
      (node (ref "U2") (pin "12") (pinfunction "RCLK/LATCH_12") (pintype "input"))
      (node (ref "U3") (pin "5") (pinfunction "RC4/ANC4_5") (pintype "bidirectional"))
      (node (ref "U4") (pin "12") (pinfunction "RCLK/LATCH_12") (pintype "input"))
    )
    (net (code "9") (name "/MCLR") (class "Default")
      (node (ref "J1") (pin "1") (pinfunction "~{MCLR}_1") (pintype "passive"))
      (node (ref "R11") (pin "1") (pinfunction "1_1") (pintype "passive"))
      (node (ref "U3") (pin "3") (pinfunction "RA3/~{MCL}R_3") (pintype "bidirectional"))
    )
    (net (code "10") (name "/N1") (class "Default")
      (node (ref "Q10") (pin "1") (pinfunction "G_1") (pintype "passive"))
      (node (ref "TP9") (pin "1") (pinfunction "A_1") (pintype "passive"))
      (node (ref "U4") (pin "15") (pinfunction "QA_15") (pintype "bidirectional"))
    )
    (net (code "11") (name "/N2") (class "Default")
      (node (ref "Q11") (pin "1") (pinfunction "G_1") (pintype "passive"))
      (node (ref "U4") (pin "1") (pinfunction "QB_1") (pintype "bidirectional"))
    )
    (net (code "12") (name "/N3") (class "Default")
      (node (ref "Q12") (pin "1") (pinfunction "G_1") (pintype "passive"))
      (node (ref "U4") (pin "2") (pinfunction "QC_2") (pintype "bidirectional"))
    )
    (net (code "13") (name "/N4") (class "Default")
      (node (ref "Q13") (pin "1") (pinfunction "G_1") (pintype "passive"))
      (node (ref "U4") (pin "3") (pinfunction "QD_3") (pintype "bidirectional"))
    )
    (net (code "14") (name "/N5") (class "Default")
      (node (ref "Q14") (pin "1") (pinfunction "G_1") (pintype "passive"))
      (node (ref "U4") (pin "4") (pinfunction "QE_4") (pintype "bidirectional"))
    )
    (net (code "15") (name "/N6") (class "Default")
      (node (ref "Q15") (pin "1") (pinfunction "G_1") (pintype "passive"))
      (node (ref "U4") (pin "5") (pinfunction "QF_5") (pintype "bidirectional"))
    )
    (net (code "16") (name "/N7") (class "Default")
      (node (ref "Q16") (pin "1") (pinfunction "G_1") (pintype "passive"))
      (node (ref "U4") (pin "6") (pinfunction "QG_6") (pintype "bidirectional"))
    )
    (net (code "17") (name "/OE_n") (class "Default")
      (node (ref "TP5") (pin "1") (pinfunction "A_1") (pintype "passive"))
      (node (ref "U2") (pin "13") (pinfunction "~{OE}_13") (pintype "input"))
      (node (ref "U3") (pin "7") (pinfunction "RC2/ANC2_7") (pintype "bidirectional"))
      (node (ref "U4") (pin "13") (pinfunction "~{OE}_13") (pintype "input"))
    )
    (net (code "18") (name "/P1") (class "Default")
      (node (ref "Q1") (pin "1") (pinfunction "G_1") (pintype "passive"))
      (node (ref "TP10") (pin "1") (pinfunction "A_1") (pintype "passive"))
      (node (ref "U2") (pin "15") (pinfunction "QA_15") (pintype "bidirectional"))
    )
    (net (code "19") (name "/P2") (class "Default")
      (node (ref "Q3") (pin "1") (pinfunction "G_1") (pintype "passive"))
      (node (ref "U2") (pin "1") (pinfunction "QB_1") (pintype "bidirectional"))
    )
    (net (code "20") (name "/P3") (class "Default")
      (node (ref "Q4") (pin "1") (pinfunction "G_1") (pintype "passive"))
      (node (ref "U2") (pin "2") (pinfunction "QC_2") (pintype "bidirectional"))
    )
    (net (code "21") (name "/P4") (class "Default")
      (node (ref "Q5") (pin "1") (pinfunction "G_1") (pintype "passive"))
      (node (ref "U2") (pin "3") (pinfunction "QD_3") (pintype "bidirectional"))
    )
    (net (code "22") (name "/P5") (class "Default")
      (node (ref "Q6") (pin "1") (pinfunction "G_1") (pintype "passive"))
      (node (ref "U2") (pin "4") (pinfunction "QE_4") (pintype "bidirectional"))
    )
    (net (code "23") (name "/P6") (class "Default")
      (node (ref "Q7") (pin "1") (pinfunction "G_1") (pintype "passive"))
      (node (ref "U2") (pin "5") (pinfunction "QF_5") (pintype "bidirectional"))
    )
    (net (code "24") (name "/P7") (class "Default")
      (node (ref "Q8") (pin "1") (pinfunction "G_1") (pintype "passive"))
      (node (ref "U2") (pin "6") (pinfunction "QG_6") (pintype "bidirectional"))
    )
    (net (code "25") (name "/PGC") (class "Default")
      (node (ref "J1") (pin "5") (pinfunction "PGC_5") (pintype "passive"))
      (node (ref "U3") (pin "11") (pinfunction "RA1/ICSPCLK_11") (pintype "bidirectional"))
    )
    (net (code "26") (name "/PGD") (class "Default")
      (node (ref "J1") (pin "4") (pinfunction "PGD_4") (pintype "passive"))
      (node (ref "U3") (pin "12") (pinfunction "RA0/ICSPDAT_12") (pintype "bidirectional"))
    )
    (net (code "27") (name "/SWITCH") (class "Default")
      (node (ref "R7") (pin "2") (pinfunction "2_2") (pintype "passive"))
      (node (ref "S2") (pin "3") (pinfunction "3_3") (pintype "passive"))
      (node (ref "S2") (pin "4") (pinfunction "4_4") (pintype "passive"))
      (node (ref "U3") (pin "10") (pinfunction "RA2/ANA2/INT_10") (pintype "bidirectional"))
    )
    (net (code "28") (name "GND") (class "Default")
      (node (ref "B1") (pin "2") (pinfunction "-_2") (pintype "passive"))
      (node (ref "C1") (pin "1") (pinfunction "1_1") (pintype "passive"))
      (node (ref "C2") (pin "1") (pinfunction "1_1") (pintype "passive"))
      (node (ref "C3") (pin "1") (pinfunction "1_1") (pintype "passive"))
      (node (ref "C4") (pin "1") (pinfunction "1_1") (pintype "passive"))
      (node (ref "C5") (pin "1") (pinfunction "1_1") (pintype "passive"))
      (node (ref "C6") (pin "1") (pinfunction "1_1") (pintype "passive"))
      (node (ref "J1") (pin "3") (pinfunction "GND_3") (pintype "passive"))
      (node (ref "Q10") (pin "2") (pinfunction "S_2") (pintype "passive"))
      (node (ref "Q11") (pin "2") (pinfunction "S_2") (pintype "passive"))
      (node (ref "Q12") (pin "2") (pinfunction "S_2") (pintype "passive"))
      (node (ref "Q13") (pin "2") (pinfunction "S_2") (pintype "passive"))
      (node (ref "Q14") (pin "2") (pinfunction "S_2") (pintype "passive"))
      (node (ref "Q15") (pin "2") (pinfunction "S_2") (pintype "passive"))
      (node (ref "Q16") (pin "2") (pinfunction "S_2") (pintype "passive"))
      (node (ref "Q9") (pin "2") (pinfunction "S_2") (pintype "passive"))
      (node (ref "R7") (pin "1") (pinfunction "1_1") (pintype "passive"))
      (node (ref "U1") (pin "3") (pinfunction "GND_3") (pintype "power_in"))
      (node (ref "U1") (pin "7") (pinfunction "TH_7") (pintype "passive"))
      (node (ref "U2") (pin "17") (pinfunction "TH_17") (pintype "power_in"))
      (node (ref "U2") (pin "8") (pinfunction "GND_8") (pintype "power_in"))
      (node (ref "U3") (pin "13") (pinfunction "VSS_13") (pintype "power_in"))
      (node (ref "U3") (pin "17") (pinfunction "TH_17") (pintype "power_in"))
      (node (ref "U4") (pin "17") (pinfunction "TH_17") (pintype "power_in"))
      (node (ref "U4") (pin "8") (pinfunction "GND_8") (pintype "power_in"))
    )
    (net (code "29") (name "Net-(D1-A)") (class "Default")
      (node (ref "D1") (pin "1") (pinfunction "A_1") (pintype "passive"))
      (node (ref "D2") (pin "1") (pinfunction "A_1") (pintype "passive"))
      (node (ref "D3") (pin "1") (pinfunction "A_1") (pintype "passive"))
      (node (ref "D4") (pin "1") (pinfunction "A_1") (pintype "passive"))
      (node (ref "D5") (pin "1") (pinfunction "A_1") (pintype "passive"))
      (node (ref "D6") (pin "1") (pinfunction "A_1") (pintype "passive"))
      (node (ref "D7") (pin "1") (pinfunction "A_1") (pintype "passive"))
      (node (ref "R2") (pin "2") (pinfunction "2_2") (pintype "passive"))
    )
    (net (code "30") (name "Net-(D1-K)") (class "Default")
      (node (ref "D1") (pin "2") (pinfunction "K_2") (pintype "passive"))
      (node (ref "D15") (pin "2") (pinfunction "K_2") (pintype "passive"))
      (node (ref "D22") (pin "2") (pinfunction "K_2") (pintype "passive"))
      (node (ref "D30") (pin "2") (pinfunction "K_2") (pintype "passive"))
      (node (ref "D36") (pin "2") (pinfunction "K_2") (pintype "passive"))
      (node (ref "D43") (pin "2") (pinfunction "K_2") (pintype "passive"))
      (node (ref "D8") (pin "2") (pinfunction "K_2") (pintype "passive"))
      (node (ref "Q10") (pin "3") (pinfunction "D_3") (pintype "passive"))
    )
    (net (code "31") (name "Net-(D10-A)") (class "Default")
      (node (ref "D10") (pin "1") (pinfunction "A_1") (pintype "passive"))
      (node (ref "D11") (pin "1") (pinfunction "A_1") (pintype "passive"))
      (node (ref "D12") (pin "1") (pinfunction "A_1") (pintype "passive"))
      (node (ref "D13") (pin "1") (pinfunction "A_1") (pintype "passive"))
      (node (ref "D14") (pin "1") (pinfunction "A_1") (pintype "passive"))
      (node (ref "D8") (pin "1") (pinfunction "A_1") (pintype "passive"))
      (node (ref "D9") (pin "1") (pinfunction "A_1") (pintype "passive"))
      (node (ref "R3") (pin "2") (pinfunction "2_2") (pintype "passive"))
    )
    (net (code "32") (name "Net-(D10-K)") (class "Default")
      (node (ref "D10") (pin "2") (pinfunction "K_2") (pintype "passive"))
      (node (ref "D17") (pin "2") (pinfunction "K_2") (pintype "passive"))
      (node (ref "D24") (pin "2") (pinfunction "K_2") (pintype "passive"))
      (node (ref "D3") (pin "2") (pinfunction "K_2") (pintype "passive"))
      (node (ref "D32") (pin "2") (pinfunction "K_2") (pintype "passive"))
      (node (ref "D38") (pin "2") (pinfunction "K_2") (pintype "passive"))
      (node (ref "D45") (pin "2") (pinfunction "K_2") (pintype "passive"))
      (node (ref "Q12") (pin "3") (pinfunction "D_3") (pintype "passive"))
    )
    (net (code "33") (name "Net-(D11-K)") (class "Default")
      (node (ref "D11") (pin "2") (pinfunction "K_2") (pintype "passive"))
      (node (ref "D18") (pin "2") (pinfunction "K_2") (pintype "passive"))
      (node (ref "D25") (pin "2") (pinfunction "K_2") (pintype "passive"))
      (node (ref "D33") (pin "2") (pinfunction "K_2") (pintype "passive"))
      (node (ref "D39") (pin "2") (pinfunction "K_2") (pintype "passive"))
      (node (ref "D4") (pin "2") (pinfunction "K_2") (pintype "passive"))
      (node (ref "D46") (pin "2") (pinfunction "K_2") (pintype "passive"))
      (node (ref "Q13") (pin "3") (pinfunction "D_3") (pintype "passive"))
    )
    (net (code "34") (name "Net-(D12-K)") (class "Default")
      (node (ref "D12") (pin "2") (pinfunction "K_2") (pintype "passive"))
      (node (ref "D19") (pin "2") (pinfunction "K_2") (pintype "passive"))
      (node (ref "D26") (pin "2") (pinfunction "K_2") (pintype "passive"))
      (node (ref "D29") (pin "2") (pinfunction "K_2") (pintype "passive"))
      (node (ref "D40") (pin "2") (pinfunction "K_2") (pintype "passive"))
      (node (ref "D47") (pin "2") (pinfunction "K_2") (pintype "passive"))
      (node (ref "D5") (pin "2") (pinfunction "K_2") (pintype "passive"))
      (node (ref "Q14") (pin "3") (pinfunction "D_3") (pintype "passive"))
    )
    (net (code "35") (name "Net-(D13-K)") (class "Default")
      (node (ref "D13") (pin "2") (pinfunction "K_2") (pintype "passive"))
      (node (ref "D20") (pin "2") (pinfunction "K_2") (pintype "passive"))
      (node (ref "D27") (pin "2") (pinfunction "K_2") (pintype "passive"))
      (node (ref "D34") (pin "2") (pinfunction "K_2") (pintype "passive"))
      (node (ref "D41") (pin "2") (pinfunction "K_2") (pintype "passive"))
      (node (ref "D48") (pin "2") (pinfunction "K_2") (pintype "passive"))
      (node (ref "D6") (pin "2") (pinfunction "K_2") (pintype "passive"))
      (node (ref "Q15") (pin "3") (pinfunction "D_3") (pintype "passive"))
    )
    (net (code "36") (name "Net-(D14-K)") (class "Default")
      (node (ref "D14") (pin "2") (pinfunction "K_2") (pintype "passive"))
      (node (ref "D21") (pin "2") (pinfunction "K_2") (pintype "passive"))
      (node (ref "D28") (pin "2") (pinfunction "K_2") (pintype "passive"))
      (node (ref "D35") (pin "2") (pinfunction "K_2") (pintype "passive"))
      (node (ref "D42") (pin "2") (pinfunction "K_2") (pintype "passive"))
      (node (ref "D49") (pin "2") (pinfunction "K_2") (pintype "passive"))
      (node (ref "D7") (pin "2") (pinfunction "K_2") (pintype "passive"))
      (node (ref "Q16") (pin "3") (pinfunction "D_3") (pintype "passive"))
    )
    (net (code "37") (name "Net-(D15-A)") (class "Default")
      (node (ref "D15") (pin "1") (pinfunction "A_1") (pintype "passive"))
      (node (ref "D16") (pin "1") (pinfunction "A_1") (pintype "passive"))
      (node (ref "D17") (pin "1") (pinfunction "A_1") (pintype "passive"))
      (node (ref "D18") (pin "1") (pinfunction "A_1") (pintype "passive"))
      (node (ref "D19") (pin "1") (pinfunction "A_1") (pintype "passive"))
      (node (ref "D20") (pin "1") (pinfunction "A_1") (pintype "passive"))
      (node (ref "D21") (pin "1") (pinfunction "A_1") (pintype "passive"))
      (node (ref "R4") (pin "2") (pinfunction "2_2") (pintype "passive"))
    )
    (net (code "38") (name "Net-(D16-K)") (class "Default")
      (node (ref "D16") (pin "2") (pinfunction "K_2") (pintype "passive"))
      (node (ref "D2") (pin "2") (pinfunction "K_2") (pintype "passive"))
      (node (ref "D23") (pin "2") (pinfunction "K_2") (pintype "passive"))
      (node (ref "D31") (pin "2") (pinfunction "K_2") (pintype "passive"))
      (node (ref "D37") (pin "2") (pinfunction "K_2") (pintype "passive"))
      (node (ref "D44") (pin "2") (pinfunction "K_2") (pintype "passive"))
      (node (ref "D9") (pin "2") (pinfunction "K_2") (pintype "passive"))
      (node (ref "Q11") (pin "3") (pinfunction "D_3") (pintype "passive"))
    )
    (net (code "39") (name "Net-(D22-A)") (class "Default")
      (node (ref "D22") (pin "1") (pinfunction "A_1") (pintype "passive"))
      (node (ref "D23") (pin "1") (pinfunction "A_1") (pintype "passive"))
      (node (ref "D24") (pin "1") (pinfunction "A_1") (pintype "passive"))
      (node (ref "D25") (pin "1") (pinfunction "A_1") (pintype "passive"))
      (node (ref "D26") (pin "1") (pinfunction "A_1") (pintype "passive"))
      (node (ref "D27") (pin "1") (pinfunction "A_1") (pintype "passive"))
      (node (ref "D28") (pin "1") (pinfunction "A_1") (pintype "passive"))
      (node (ref "R5") (pin "2") (pinfunction "2_2") (pintype "passive"))
    )
    (net (code "40") (name "Net-(D29-A)") (class "Default")
      (node (ref "D29") (pin "1") (pinfunction "A_1") (pintype "passive"))
      (node (ref "D30") (pin "1") (pinfunction "A_1") (pintype "passive"))
      (node (ref "D31") (pin "1") (pinfunction "A_1") (pintype "passive"))
      (node (ref "D32") (pin "1") (pinfunction "A_1") (pintype "passive"))
      (node (ref "D33") (pin "1") (pinfunction "A_1") (pintype "passive"))
      (node (ref "D34") (pin "1") (pinfunction "A_1") (pintype "passive"))
      (node (ref "D35") (pin "1") (pinfunction "A_1") (pintype "passive"))
      (node (ref "R6") (pin "2") (pinfunction "2_2") (pintype "passive"))
    )
    (net (code "41") (name "Net-(D36-A)") (class "Default")
      (node (ref "D36") (pin "1") (pinfunction "A_1") (pintype "passive"))
      (node (ref "D37") (pin "1") (pinfunction "A_1") (pintype "passive"))
      (node (ref "D38") (pin "1") (pinfunction "A_1") (pintype "passive"))
      (node (ref "D39") (pin "1") (pinfunction "A_1") (pintype "passive"))
      (node (ref "D40") (pin "1") (pinfunction "A_1") (pintype "passive"))
      (node (ref "D41") (pin "1") (pinfunction "A_1") (pintype "passive"))
      (node (ref "D42") (pin "1") (pinfunction "A_1") (pintype "passive"))
      (node (ref "R8") (pin "2") (pinfunction "2_2") (pintype "passive"))
    )
    (net (code "42") (name "Net-(D43-A)") (class "Default")
      (node (ref "D43") (pin "1") (pinfunction "A_1") (pintype "passive"))
      (node (ref "D44") (pin "1") (pinfunction "A_1") (pintype "passive"))
      (node (ref "D45") (pin "1") (pinfunction "A_1") (pintype "passive"))
      (node (ref "D46") (pin "1") (pinfunction "A_1") (pintype "passive"))
      (node (ref "D47") (pin "1") (pinfunction "A_1") (pintype "passive"))
      (node (ref "D48") (pin "1") (pinfunction "A_1") (pintype "passive"))
      (node (ref "D49") (pin "1") (pinfunction "A_1") (pintype "passive"))
      (node (ref "R10") (pin "2") (pinfunction "2_2") (pintype "passive"))
    )
    (net (code "43") (name "Net-(LS1--)") (class "Default")
      (node (ref "LS1") (pin "2") (pinfunction "-_2") (pintype "power_in"))
      (node (ref "Q9") (pin "3") (pinfunction "D_3") (pintype "passive"))
      (node (ref "R9") (pin "1") (pinfunction "1_1") (pintype "passive"))
    )
    (net (code "44") (name "Net-(Q1-D)") (class "Default")
      (node (ref "Q1") (pin "3") (pinfunction "D_3") (pintype "passive"))
      (node (ref "R2") (pin "1") (pinfunction "1_1") (pintype "passive"))
    )
    (net (code "45") (name "Net-(Q3-D)") (class "Default")
      (node (ref "Q3") (pin "3") (pinfunction "D_3") (pintype "passive"))
      (node (ref "R3") (pin "1") (pinfunction "1_1") (pintype "passive"))
    )
    (net (code "46") (name "Net-(Q4-D)") (class "Default")
      (node (ref "Q4") (pin "3") (pinfunction "D_3") (pintype "passive"))
      (node (ref "R4") (pin "1") (pinfunction "1_1") (pintype "passive"))
    )
    (net (code "47") (name "Net-(Q5-D)") (class "Default")
      (node (ref "Q5") (pin "3") (pinfunction "D_3") (pintype "passive"))
      (node (ref "R5") (pin "1") (pinfunction "1_1") (pintype "passive"))
    )
    (net (code "48") (name "Net-(Q6-D)") (class "Default")
      (node (ref "Q6") (pin "3") (pinfunction "D_3") (pintype "passive"))
      (node (ref "R6") (pin "1") (pinfunction "1_1") (pintype "passive"))
    )
    (net (code "49") (name "Net-(Q7-D)") (class "Default")
      (node (ref "Q7") (pin "3") (pinfunction "D_3") (pintype "passive"))
      (node (ref "R8") (pin "1") (pinfunction "1_1") (pintype "passive"))
    )
    (net (code "50") (name "Net-(Q8-D)") (class "Default")
      (node (ref "Q8") (pin "3") (pinfunction "D_3") (pintype "passive"))
      (node (ref "R10") (pin "1") (pinfunction "1_1") (pintype "passive"))
    )
    (net (code "51") (name "Net-(Q9-G)") (class "Default")
      (node (ref "Q9") (pin "1") (pinfunction "G_1") (pintype "passive"))
      (node (ref "TP4") (pin "1") (pinfunction "A_1") (pintype "passive"))
      (node (ref "U3") (pin "1") (pinfunction "RA5/ANA5_1") (pintype "bidirectional"))
    )
    (net (code "52") (name "Net-(U1-EN)") (class "Default")
      (node (ref "C1") (pin "2") (pinfunction "2_2") (pintype "passive"))
      (node (ref "S1") (pin "1") (pintype "passive"))
      (node (ref "U1") (pin "4") (pinfunction "VIN_4") (pintype "power_in"))
      (node (ref "U1") (pin "6") (pinfunction "EN_6") (pintype "input"))
    )
    (net (code "53") (name "unconnected-(J1-NC-Pad6)") (class "Default")
      (node (ref "J1") (pin "6") (pinfunction "NC_6") (pintype "passive+no_connect"))
    )
    (net (code "54") (name "unconnected-(MH1-Pad1)") (class "Default")
      (node (ref "MH1") (pin "1") (pinfunction "1_1") (pintype "passive"))
    )
    (net (code "55") (name "unconnected-(S1-Pad3)") (class "Default")
      (node (ref "S1") (pin "3") (pintype "passive"))
    )
    (net (code "56") (name "unconnected-(U1-NC-Pad1)") (class "Default")
      (node (ref "U1") (pin "1") (pinfunction "NC_1") (pintype "passive+no_connect"))
    )
    (net (code "57") (name "unconnected-(U1-NC-Pad2)") (class "Default")
      (node (ref "U1") (pin "2") (pinfunction "NC_2") (pintype "passive+no_connect"))
    )
    (net (code "58") (name "unconnected-(U2-QH-Pad7)") (class "Default")
      (node (ref "U2") (pin "7") (pinfunction "QH_7") (pintype "bidirectional+no_connect"))
    )
    (net (code "59") (name "unconnected-(U3-NC-Pad14)") (class "Default")
      (node (ref "U3") (pin "14") (pinfunction "NC_14") (pintype "passive+no_connect"))
    )
    (net (code "60") (name "unconnected-(U3-NC-Pad15)") (class "Default")
      (node (ref "U3") (pin "15") (pinfunction "NC_15") (pintype "passive+no_connect"))
    )
    (net (code "61") (name "unconnected-(U3-RA4{slash}ANA4-Pad2)") (class "Default")
      (node (ref "U3") (pin "2") (pinfunction "RA4/ANA4_2") (pintype "bidirectional"))
    )
    (net (code "62") (name "unconnected-(U3-RC1{slash}SDA1{slash}SDI1-Pad8)") (class "Default")
      (node (ref "U3") (pin "8") (pinfunction "RC1/SDA1/SDI1_8") (pintype "bidirectional"))
    )
    (net (code "63") (name "unconnected-(U4-QH'-Pad9)") (class "Default")
      (node (ref "U4") (pin "9") (pinfunction "QH'_9") (pintype "input+no_connect"))
    )
    (net (code "64") (name "unconnected-(U4-QH-Pad7)") (class "Default")
      (node (ref "U4") (pin "7") (pinfunction "QH_7") (pintype "bidirectional+no_connect"))
    )
  )
)
